# EV75E52A_R3_2-PHYs.net
KiCad netlist of a schematic drawn in Altium Designer
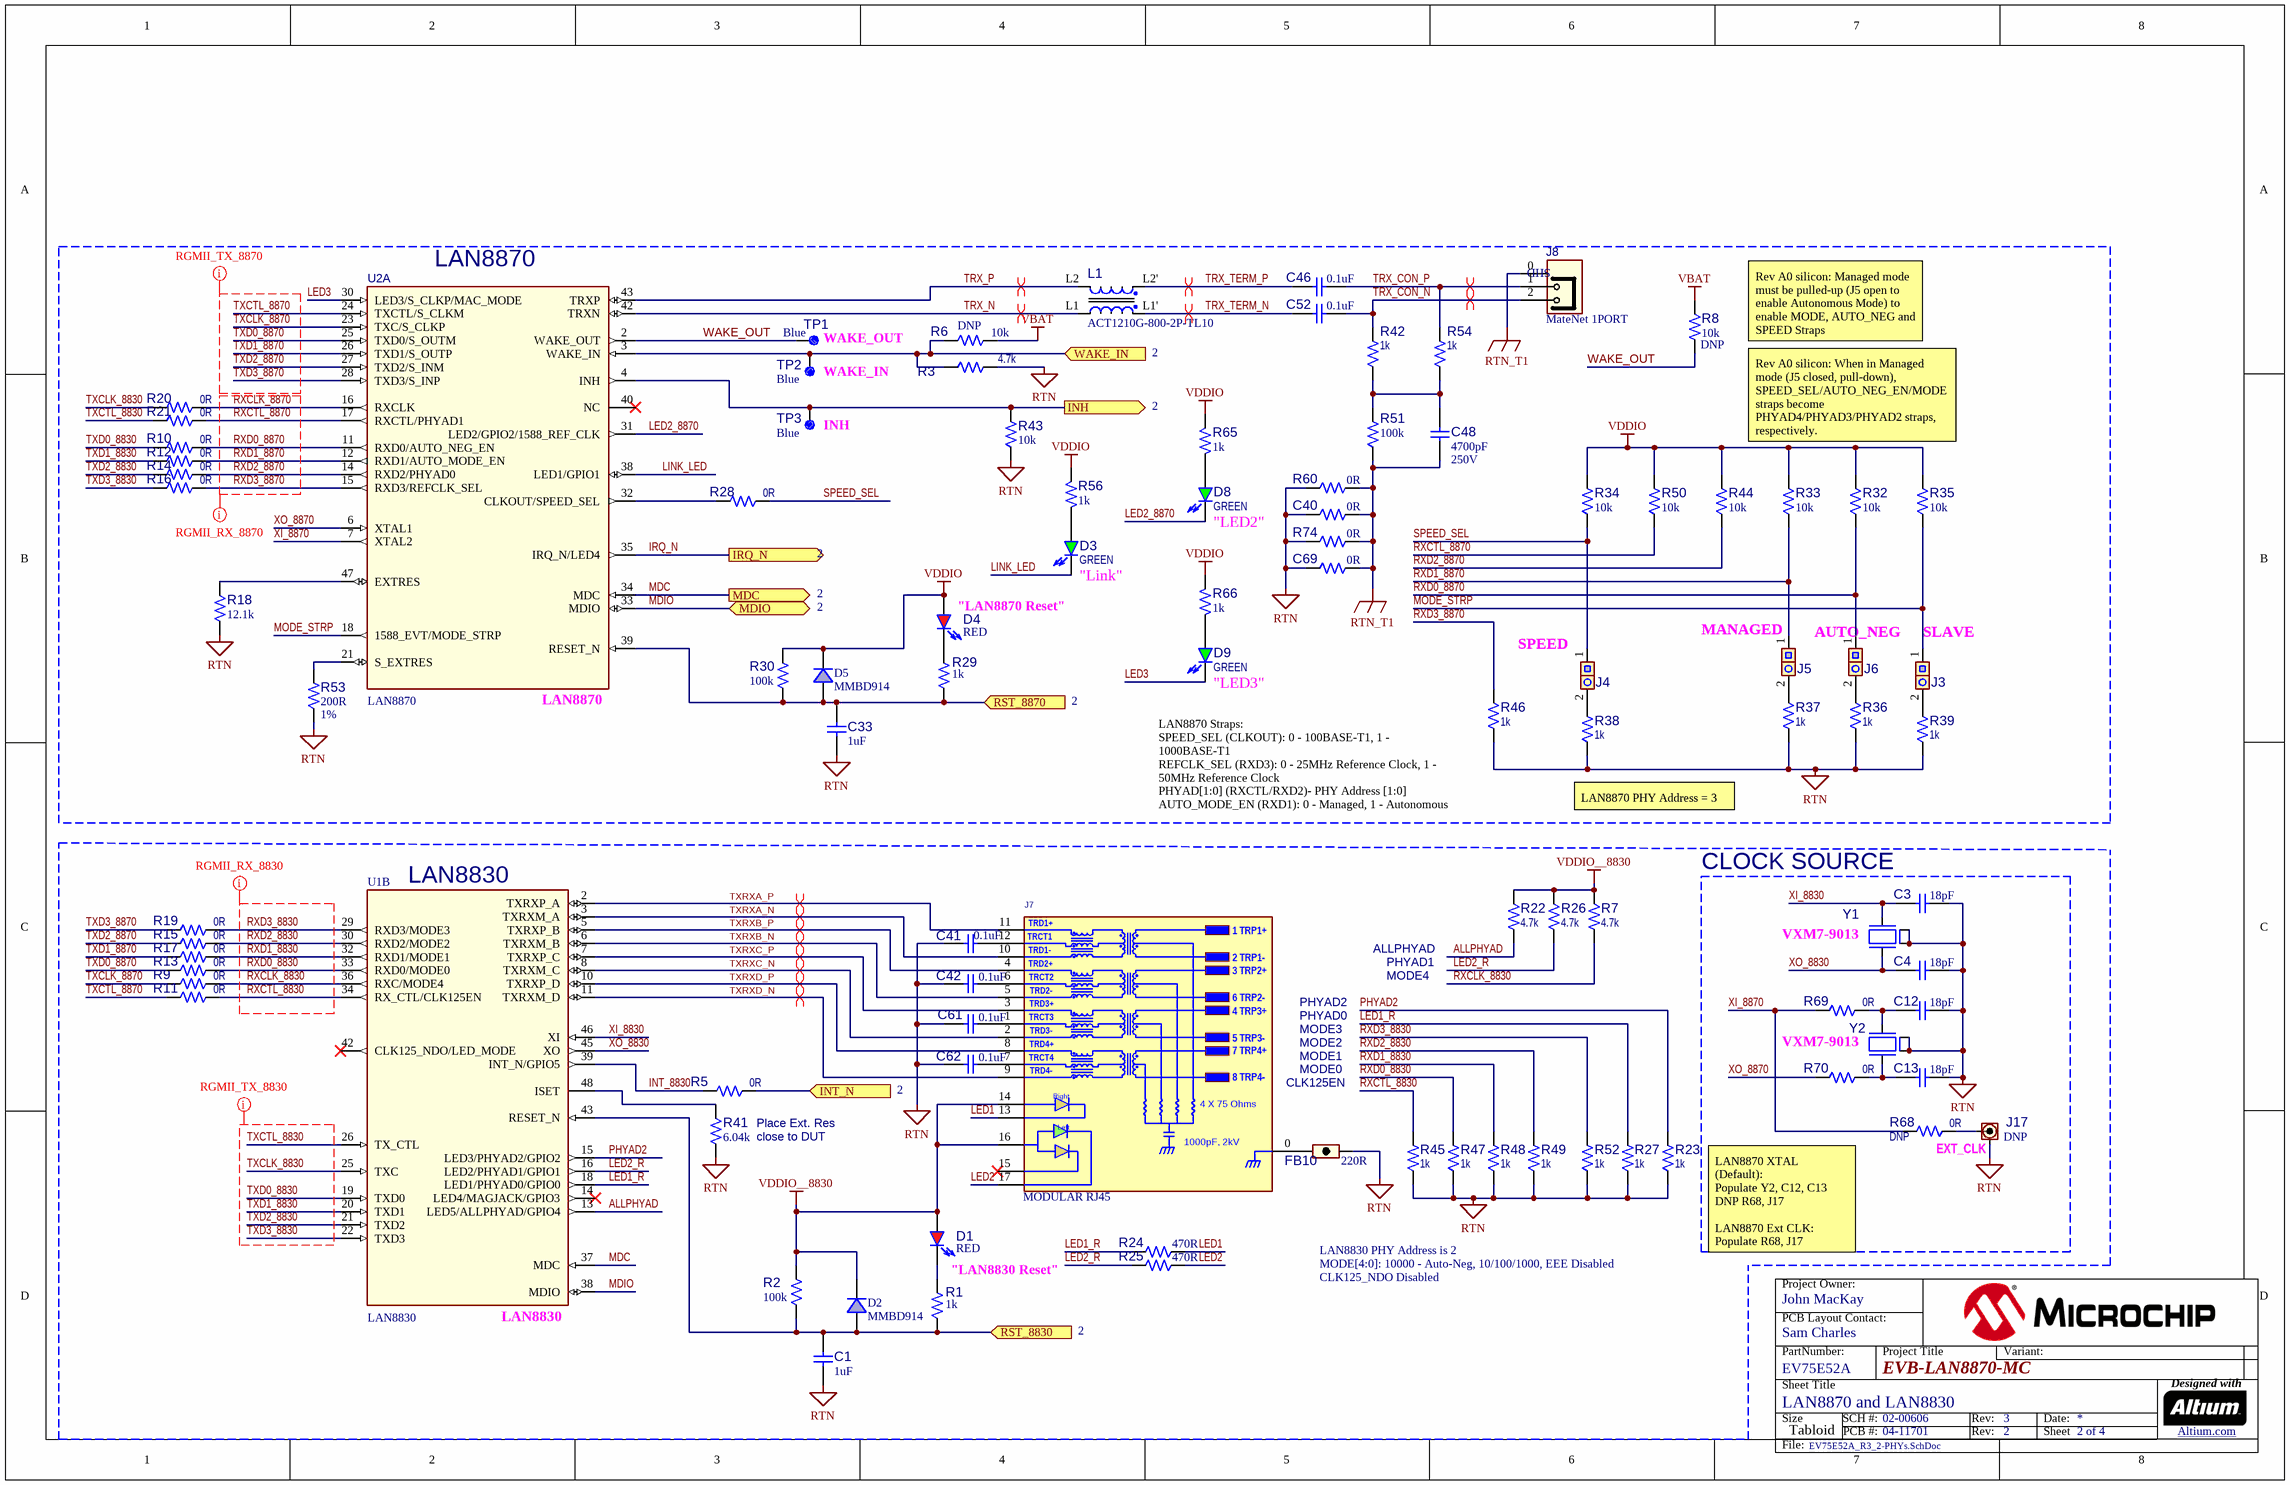
[diagram p0: EV75E52A_R3_2-PHYs.SchDoc]

(export (version "E")
  (design (tool "Eeschema 10.0.6"))
  (components
    (comp (ref "C1")
      (value "1uF")
      (footprint "CAP_C_0603")
      (description "Capacitor")
      (fields (field (name "VOLTAGE") "16V") (field (name "TOLERANCE") "10%"))
      (libsource (lib "MCHP-CDB") (part "Capacitor NP"))
    )
    (comp (ref "C3")
      (value "18pF")
      (footprint "CAP_C_0402")
      (description "Capacitor")
      (fields
        (field (name "VOLTAGE") "50V")
        (field (name "TOLERANCE") "5%")
        (field (name "OWNER") "Tad Ahlvers")
      )
      (libsource (lib "MCHP-CDB") (part "Capacitor NP"))
    )
    (comp (ref "C4")
      (value "18pF")
      (footprint "CAP_C_0402")
      (description "Capacitor")
      (fields
        (field (name "VOLTAGE") "50V")
        (field (name "TOLERANCE") "5%")
        (field (name "OWNER") "Tad Ahlvers")
      )
      (libsource (lib "MCHP-CDB") (part "Capacitor NP"))
    )
    (comp (ref "C12")
      (value "18pF")
      (footprint "CAP_C_0402")
      (description "Capacitor")
      (fields
        (field (name "VOLTAGE") "50V")
        (field (name "TOLERANCE") "5%")
        (field (name "OWNER") "Tad Ahlvers")
      )
      (libsource (lib "MCHP-CDB") (part "Capacitor NP"))
    )
    (comp (ref "C13")
      (value "18pF")
      (footprint "CAP_C_0402")
      (description "Capacitor")
      (fields
        (field (name "VOLTAGE") "50V")
        (field (name "TOLERANCE") "5%")
        (field (name "OWNER") "Tad Ahlvers")
      )
      (libsource (lib "MCHP-CDB") (part "Capacitor NP"))
    )
    (comp (ref "C33")
      (value "1uF")
      (footprint "CAP_C_0603")
      (description "Capacitor")
      (fields (field (name "VOLTAGE") "16V") (field (name "TOLERANCE") "10%"))
      (libsource (lib "MCHP-CDB") (part "Capacitor NP"))
    )
    (comp (ref "C40")
      (value "0R")
      (footprint "RES_C_0603")
      (description "Resistor")
      (fields (field (name "POWER") "1/10W") (field (name "OWNER") "Steve Dziaba"))
      (libsource (lib "MCHP-CDB") (part "Resistor"))
    )
    (comp (ref "C41")
      (value "0.1uF")
      (footprint "CAP_C_0402")
      (description "Capacitor")
      (fields
        (field (name "TOLERANCE") "10%")
        (field (name "VOLTAGE") "50V")
        (field (name "OWNER") "Jamus Griego")
      )
      (libsource (lib "MCHP-CDB-Offline") (part "Capacitor NP"))
    )
    (comp (ref "C42")
      (value "0.1uF")
      (footprint "CAP_C_0402")
      (description "Capacitor")
      (fields
        (field (name "TOLERANCE") "10%")
        (field (name "VOLTAGE") "50V")
        (field (name "OWNER") "Jamus Griego")
      )
      (libsource (lib "MCHP-CDB-Offline") (part "Capacitor NP"))
    )
    (comp (ref "C46")
      (value "0.1uF")
      (footprint "CAP_C_0805")
      (description "Capacitor")
      (fields
        (field (name "VOLTAGE") "250V")
        (field (name "TOLERANCE") "10%")
        (field (name "OWNER") "Cristian Papuc")
      )
      (libsource (lib "MCHP-CDB") (part "Capacitor NP"))
    )
    (comp (ref "C48")
      (value "4700pF")
      (footprint "CAP_C_0805")
      (fields
        (field (name "VOLTAGE") "250V")
        (field (name "TOLERANCE") "10%")
        (field (name "Comment") "Capacitor NP")
        (field (name "OWNER") "Darius Rydahl")
      )
      (libsource (lib "") (part "Capacitor NP_1"))
    )
    (comp (ref "C52")
      (value "0.1uF")
      (footprint "CAP_C_0805")
      (description "Capacitor")
      (fields
        (field (name "VOLTAGE") "250V")
        (field (name "TOLERANCE") "10%")
        (field (name "OWNER") "Cristian Papuc")
      )
      (libsource (lib "MCHP-CDB") (part "Capacitor NP"))
    )
    (comp (ref "C61")
      (value "0.1uF")
      (footprint "CAP_C_0402")
      (description "Capacitor")
      (fields
        (field (name "TOLERANCE") "10%")
        (field (name "VOLTAGE") "50V")
        (field (name "OWNER") "Jamus Griego")
      )
      (libsource (lib "MCHP-CDB-Offline") (part "Capacitor NP"))
    )
    (comp (ref "C62")
      (value "0.1uF")
      (footprint "CAP_C_0402")
      (description "Capacitor")
      (fields
        (field (name "TOLERANCE") "10%")
        (field (name "VOLTAGE") "50V")
        (field (name "OWNER") "Jamus Griego")
      )
      (libsource (lib "MCHP-CDB-Offline") (part "Capacitor NP"))
    )
    (comp (ref "C69")
      (value "0R")
      (footprint "RES_C_0603")
      (description "Resistor")
      (fields (field (name "POWER") "1/10W") (field (name "OWNER") "Steve Dziaba"))
      (libsource (lib "MCHP-CDB") (part "Resistor"))
    )
    (comp (ref "D1")
      (value "RED")
      (footprint "LED_0603_RED")
      (description "LED")
      (fields
        (field (name "LEGEND NOTE") "\"LAN8830 Reset\"")
        (field (name "Comment") "LED_red")
        (field (name "OWNER") "Sompoch Loboonlert")
      )
      (libsource (lib "MCHP-CDB") (part "LED_red"))
    )
    (comp (ref "D2")
      (value "MMBD914")
      (footprint "SOT-23-3")
      (fields (field (name "POWER") "10mW") (field (name "OWNER") "Sam Charles"))
      (libsource (lib "MCHP-CDB") (part "Diode Single SOT-23-3"))
    )
    (comp (ref "D3")
      (value "GREEN")
      (footprint "LED_0603_GREEN")
      (description "LED")
      (fields
        (field (name "POWER") "75mW")
        (field (name "LEGEND NOTES") "\"Link\"")
        (field (name "Comment") "LED_green")
        (field (name "OWNER") "Tad Ahlvers")
      )
      (libsource (lib "MCHP-CDB") (part "LED_green"))
    )
    (comp (ref "D4")
      (value "RED")
      (footprint "LED_0603_RED")
      (description "LED")
      (fields
        (field (name "LEGEND NOTE") "\"LAN8870 Reset\"")
        (field (name "Comment") "LED_red")
        (field (name "OWNER") "Sompoch Loboonlert")
      )
      (libsource (lib "MCHP-CDB") (part "LED_red"))
    )
    (comp (ref "D5")
      (value "MMBD914")
      (footprint "SOT-23-3")
      (fields (field (name "POWER") "10mW") (field (name "OWNER") "Sam Charles"))
      (libsource (lib "MCHP-CDB") (part "Diode Single SOT-23-3"))
    )
    (comp (ref "D8")
      (value "GREEN")
      (footprint "LED_0603_GREEN")
      (description "LED")
      (fields
        (field (name "POWER") "75mW")
        (field (name "LEGEND NOTES") "\"LED2\"")
        (field (name "Comment") "LED_green")
        (field (name "OWNER") "Tad Ahlvers")
      )
      (libsource (lib "MCHP-CDB") (part "LED_green"))
    )
    (comp (ref "D9")
      (value "GREEN")
      (footprint "LED_0603_GREEN")
      (description "LED")
      (fields
        (field (name "POWER") "75mW")
        (field (name "LEGEND NOTES") "\"LED3\"")
        (field (name "Comment") "LED_green")
        (field (name "OWNER") "Tad Ahlvers")
      )
      (libsource (lib "MCHP-CDB") (part "LED_green"))
    )
    (comp (ref "FB10")
      (value "220R")
      (footprint "IND_C_0603")
      (description "FERRITE 180R 1.5A SMD 0603")
      (fields (field (name "Comment") "Ferrite Bead") (field (name "OWNER") "Sam Charles"))
      (libsource (lib "MCHP-CDB") (part "Ferrite Bead"))
    )
    (comp (ref "J3")
      (value "Header 1x2")
      (footprint "HDR_M_2.54_1x2")
      (fields (field (name "LEGEND NOTES") "SLAVE") (field (name "OWNER") "Bogdan P (M91398)"))
      (libsource (lib "MCHP-CDB") (part "Header 1x2"))
    )
    (comp (ref "J4")
      (value "Header 1x2")
      (footprint "HDR_M_2.54_1x2")
      (fields (field (name "LEGEND NOTES") "SPEED") (field (name "OWNER") "Bogdan P (M91398)"))
      (libsource (lib "MCHP-CDB") (part "Header 1x2"))
    )
    (comp (ref "J5")
      (value "Header 1x2")
      (footprint "HDR_M_2.54_1x2")
      (fields (field (name "LEGEND NOTES") "MANAGED") (field (name "OWNER") "Bogdan P (M91398)"))
      (libsource (lib "MCHP-CDB") (part "Header 1x2"))
    )
    (comp (ref "J6")
      (value "Header 1x2")
      (footprint "HDR_M_2.54_1x2")
      (fields (field (name "LEGEND NOTES") "AUTO_NEG") (field (name "OWNER") "Bogdan P (M91398)"))
      (libsource (lib "MCHP-CDB") (part "Header 1x2"))
    )
    (comp (ref "J7")
      (value "MODULAR RJ45")
      (footprint "CON_JACK_RJ45_L829-1J1T-43")
      (fields (field (name "Comment") "CON_RJ-45_L829-1J1T-43") (field (name "OWNER") "Sam Charles"))
      (libsource (lib "MCHP-CDB") (part "CON_RJ-45_L829-1J1T-43"))
    )
    (comp (ref "J8")
      (value "MateNet 1PORT")
      (footprint "CON_2304372-9")
      (fields (field (name "Comment") "3PIN_WSHD") (field (name "OWNER") "Sam Charles"))
      (libsource (lib "MCHP-CDB") (part "3PIN_WSHD"))
    )
    (comp (ref "J17")
      (value "RF MMCX Female")
      (footprint "CON_MMCX_CINCH_135-3701-211")
      (description "CON Jack 2 Pins")
      (fields
        (field (name "POPULATED") "DNP")
        (field (name "LEGEND NOTE") "EXT_CLK")
        (field (name "OWNER") "Sam Charles")
      )
      (libsource (lib "MCHP-CDB") (part "CON Jack 2 Pins"))
    )
    (comp (ref "L1")
      (value "Inductor Choke")
      (footprint "IND_TDK_ACT1210L-201-2P_L3.9W2.5H2.5")
      (description "Inductor")
      (fields
        (field (name "MANUFACTURER PART NUMBER 1") "ACT1210G-800-2P-TL10")
        (field (name "OWNER") "Sam Charles")
      )
      (libsource (lib "MCHP-CDB") (part "Inductor Choke"))
    )
    (comp (ref "R1")
      (value "1k")
      (footprint "RES_C_0603")
      (description "Resistor")
      (fields
        (field (name "TOLERANCE") "5%")
        (field (name "VOLTAGE") "75V")
        (field (name "OWNER") "Bogdan P (M91398)")
      )
      (libsource (lib "") (part "Resistor_1"))
    )
    (comp (ref "R2")
      (value "100k")
      (footprint "RES_C_0603")
      (description "Resistor")
      (fields (field (name "TOLERANCE") "1%") (field (name "VOLTAGE") "75V"))
      (libsource (lib "") (part "Resistor_1"))
    )
    (comp (ref "R3")
      (value "4.7k")
      (footprint "RES_C_0402")
      (description "Resistor")
      (fields
        (field (name "TOLERANCE") "1%")
        (field (name "POWER") "1/16W")
        (field (name "OWNER") "Mike Ragsdale")
      )
      (libsource (lib "") (part "Resistor_1"))
    )
    (comp (ref "R5")
      (value "0R")
      (footprint "RES_C_0402")
      (description "Resistor")
      (fields (field (name "POWER") "1/16W") (field (name "OWNER") "Sompoch Loboonlert"))
      (libsource (lib "") (part "Resistor_1"))
    )
    (comp (ref "R6")
      (value "10k")
      (footprint "RES_C_0402")
      (description "Resistor")
      (fields
        (field (name "TOLERANCE") "1%")
        (field (name "VOLTAGE") "50V")
        (field (name "POPULATED") "DNP")
        (field (name "OWNER") "Jose Garcia")
      )
      (libsource (lib "") (part "Resistor_1"))
    )
    (comp (ref "R7")
      (value "4.7k")
      (footprint "RES_C_0402")
      (description "Resistor")
      (fields
        (field (name "TOLERANCE") "1%")
        (field (name "POWER") "1/16W")
        (field (name "OWNER") "Mike Ragsdale")
      )
      (libsource (lib "") (part "Resistor_1"))
    )
    (comp (ref "R8")
      (value "10k")
      (footprint "RES_C_0402")
      (description "Resistor")
      (fields
        (field (name "TOLERANCE") "1%")
        (field (name "VOLTAGE") "50V")
        (field (name "POPULATED") "DNP")
        (field (name "OWNER") "Jose Garcia")
      )
      (libsource (lib "") (part "Resistor_1"))
    )
    (comp (ref "R9")
      (value "0R")
      (footprint "RES_C_0402")
      (description "Resistor")
      (fields (field (name "POWER") "1/16W") (field (name "OWNER") "Sompoch Loboonlert"))
      (libsource (lib "") (part "Resistor_1"))
    )
    (comp (ref "R10")
      (value "0R")
      (footprint "RES_C_0402")
      (description "Resistor")
      (fields (field (name "POWER") "1/16W") (field (name "OWNER") "Sompoch Loboonlert"))
      (libsource (lib "") (part "Resistor_1"))
    )
    (comp (ref "R11")
      (value "0R")
      (footprint "RES_C_0402")
      (description "Resistor")
      (fields (field (name "POWER") "1/16W") (field (name "OWNER") "Sompoch Loboonlert"))
      (libsource (lib "") (part "Resistor_1"))
    )
    (comp (ref "R12")
      (value "0R")
      (footprint "RES_C_0402")
      (description "Resistor")
      (fields (field (name "POWER") "1/16W") (field (name "OWNER") "Sompoch Loboonlert"))
      (libsource (lib "") (part "Resistor_1"))
    )
    (comp (ref "R13")
      (value "0R")
      (footprint "RES_C_0402")
      (description "Resistor")
      (fields (field (name "POWER") "1/16W") (field (name "OWNER") "Sompoch Loboonlert"))
      (libsource (lib "") (part "Resistor_1"))
    )
    (comp (ref "R14")
      (value "0R")
      (footprint "RES_C_0402")
      (description "Resistor")
      (fields (field (name "POWER") "1/16W") (field (name "OWNER") "Sompoch Loboonlert"))
      (libsource (lib "") (part "Resistor_1"))
    )
    (comp (ref "R15")
      (value "0R")
      (footprint "RES_C_0402")
      (description "Resistor")
      (fields (field (name "POWER") "1/16W") (field (name "OWNER") "Sompoch Loboonlert"))
      (libsource (lib "") (part "Resistor_1"))
    )
    (comp (ref "R16")
      (value "0R")
      (footprint "RES_C_0402")
      (description "Resistor")
      (fields (field (name "POWER") "1/16W") (field (name "OWNER") "Sompoch Loboonlert"))
      (libsource (lib "") (part "Resistor_1"))
    )
    (comp (ref "R17")
      (value "0R")
      (footprint "RES_C_0402")
      (description "Resistor")
      (fields (field (name "POWER") "1/16W") (field (name "OWNER") "Sompoch Loboonlert"))
      (libsource (lib "") (part "Resistor_1"))
    )
    (comp (ref "R18")
      (value "12.1k")
      (footprint "RES_C_0402")
      (description "Resistor")
      (fields
        (field (name "TOLERANCE") "1%")
        (field (name "VOLTAGE") "50V")
        (field (name "OWNER") "Mike Ragsdale")
      )
      (libsource (lib "MCHP-CDB") (part "Resistor"))
    )
    (comp (ref "R19")
      (value "0R")
      (footprint "RES_C_0402")
      (description "Resistor")
      (fields (field (name "POWER") "1/16W") (field (name "OWNER") "Sompoch Loboonlert"))
      (libsource (lib "") (part "Resistor_1"))
    )
    (comp (ref "R20")
      (value "0R")
      (footprint "RES_C_0402")
      (description "Resistor")
      (fields (field (name "POWER") "1/16W") (field (name "OWNER") "Sompoch Loboonlert"))
      (libsource (lib "") (part "Resistor_1"))
    )
    (comp (ref "R21")
      (value "0R")
      (footprint "RES_C_0402")
      (description "Resistor")
      (fields (field (name "POWER") "1/16W") (field (name "OWNER") "Sompoch Loboonlert"))
      (libsource (lib "") (part "Resistor_1"))
    )
    (comp (ref "R22")
      (value "4.7k")
      (footprint "RES_C_0402")
      (description "Resistor")
      (fields
        (field (name "TOLERANCE") "1%")
        (field (name "POWER") "1/16W")
        (field (name "OWNER") "Mike Ragsdale")
      )
      (libsource (lib "") (part "Resistor_1"))
    )
    (comp (ref "R23")
      (value "1k")
      (footprint "RES_C_0402")
      (description "Resistor")
      (fields
        (field (name "TOLERANCE") "0.1%")
        (field (name "VOLTAGE") "50V")
        (field (name "OWNER") "Jose Garcia")
      )
      (libsource (lib "") (part "Resistor_1"))
    )
    (comp (ref "R24")
      (value "470R")
      (footprint "RES_C_0402")
      (description "Resistor")
      (fields (field (name "TOLERANCE") "5%") (field (name "VOLTAGE") "50V"))
      (libsource (lib "MCHP-CDB") (part "Resistor"))
    )
    (comp (ref "R25")
      (value "470R")
      (footprint "RES_C_0402")
      (description "Resistor")
      (fields (field (name "TOLERANCE") "5%") (field (name "VOLTAGE") "50V"))
      (libsource (lib "MCHP-CDB") (part "Resistor"))
    )
    (comp (ref "R26")
      (value "4.7k")
      (footprint "RES_C_0402")
      (description "Resistor")
      (fields
        (field (name "TOLERANCE") "1%")
        (field (name "POWER") "1/16W")
        (field (name "OWNER") "Mike Ragsdale")
      )
      (libsource (lib "") (part "Resistor_1"))
    )
    (comp (ref "R27")
      (value "1k")
      (footprint "RES_C_0402")
      (description "Resistor")
      (fields
        (field (name "TOLERANCE") "0.1%")
        (field (name "VOLTAGE") "50V")
        (field (name "OWNER") "Jose Garcia")
      )
      (libsource (lib "") (part "Resistor_1"))
    )
    (comp (ref "R28")
      (value "0R")
      (footprint "RES_C_0402")
      (description "Resistor")
      (fields (field (name "POWER") "1/16W") (field (name "OWNER") "Sompoch Loboonlert"))
      (libsource (lib "") (part "Resistor_1"))
    )
    (comp (ref "R29")
      (value "1k")
      (footprint "RES_C_0603")
      (description "Resistor")
      (fields
        (field (name "TOLERANCE") "5%")
        (field (name "VOLTAGE") "75V")
        (field (name "OWNER") "Bogdan P (M91398)")
      )
      (libsource (lib "") (part "Resistor_1"))
    )
    (comp (ref "R30")
      (value "100k")
      (footprint "RES_C_0603")
      (description "Resistor")
      (fields (field (name "TOLERANCE") "1%") (field (name "VOLTAGE") "75V"))
      (libsource (lib "") (part "Resistor_1"))
    )
    (comp (ref "R32")
      (value "10k")
      (footprint "RES_C_0402")
      (description "Resistor")
      (fields
        (field (name "TOLERANCE") "1%")
        (field (name "VOLTAGE") "50V")
        (field (name "OWNER") "Jose Garcia")
      )
      (libsource (lib "") (part "Resistor_1"))
    )
    (comp (ref "R33")
      (value "10k")
      (footprint "RES_C_0402")
      (description "Resistor")
      (fields
        (field (name "TOLERANCE") "1%")
        (field (name "VOLTAGE") "50V")
        (field (name "OWNER") "Jose Garcia")
      )
      (libsource (lib "") (part "Resistor_1"))
    )
    (comp (ref "R34")
      (value "10k")
      (footprint "RES_C_0402")
      (description "Resistor")
      (fields
        (field (name "TOLERANCE") "1%")
        (field (name "VOLTAGE") "50V")
        (field (name "OWNER") "Jose Garcia")
      )
      (libsource (lib "") (part "Resistor_1"))
    )
    (comp (ref "R35")
      (value "10k")
      (footprint "RES_C_0402")
      (description "Resistor")
      (fields
        (field (name "TOLERANCE") "1%")
        (field (name "VOLTAGE") "50V")
        (field (name "OWNER") "Jose Garcia")
      )
      (libsource (lib "") (part "Resistor_1"))
    )
    (comp (ref "R36")
      (value "1k")
      (footprint "RES_C_0402")
      (description "Resistor")
      (fields
        (field (name "TOLERANCE") "0.1%")
        (field (name "VOLTAGE") "50V")
        (field (name "OWNER") "Jose Garcia")
      )
      (libsource (lib "") (part "Resistor_1"))
    )
    (comp (ref "R37")
      (value "1k")
      (footprint "RES_C_0402")
      (description "Resistor")
      (fields
        (field (name "TOLERANCE") "0.1%")
        (field (name "VOLTAGE") "50V")
        (field (name "OWNER") "Jose Garcia")
      )
      (libsource (lib "") (part "Resistor_1"))
    )
    (comp (ref "R38")
      (value "1k")
      (footprint "RES_C_0402")
      (description "Resistor")
      (fields
        (field (name "TOLERANCE") "0.1%")
        (field (name "VOLTAGE") "50V")
        (field (name "OWNER") "Jose Garcia")
      )
      (libsource (lib "") (part "Resistor_1"))
    )
    (comp (ref "R39")
      (value "1k")
      (footprint "RES_C_0402")
      (description "Resistor")
      (fields
        (field (name "TOLERANCE") "0.1%")
        (field (name "VOLTAGE") "50V")
        (field (name "OWNER") "Jose Garcia")
      )
      (libsource (lib "") (part "Resistor_1"))
    )
    (comp (ref "R41")
      (value "6.04k")
      (footprint "RES_C_0402")
      (description "Resistor")
      (fields
        (field (name "TOLERANCE") "1%")
        (field (name "VOLTAGE") "50V")
        (field (name "OWNER") "Severino Balong Jr.")
      )
      (libsource (lib "MCHP-CDB") (part "Resistor"))
    )
    (comp (ref "R42")
      (value "1k")
      (footprint "RES_C_1206")
      (description "Resistor")
      (fields
        (field (name "TOLERANCE") "1%")
        (field (name "VOLTAGE") "200V")
        (field (name "OWNER") "Mark Loper")
      )
      (libsource (lib "") (part "Resistor_1"))
    )
    (comp (ref "R43")
      (value "10k")
      (footprint "RES_C_0402")
      (description "Resistor")
      (fields
        (field (name "TOLERANCE") "1%")
        (field (name "VOLTAGE") "50V")
        (field (name "OWNER") "Jose Garcia")
      )
      (libsource (lib "") (part "Resistor_1"))
    )
    (comp (ref "R44")
      (value "10k")
      (footprint "RES_C_0402")
      (description "Resistor")
      (fields
        (field (name "TOLERANCE") "1%")
        (field (name "VOLTAGE") "50V")
        (field (name "OWNER") "Jose Garcia")
      )
      (libsource (lib "") (part "Resistor_1"))
    )
    (comp (ref "R45")
      (value "1k")
      (footprint "RES_C_0402")
      (description "Resistor")
      (fields
        (field (name "TOLERANCE") "0.1%")
        (field (name "VOLTAGE") "50V")
        (field (name "OWNER") "Jose Garcia")
      )
      (libsource (lib "") (part "Resistor_1"))
    )
    (comp (ref "R46")
      (value "1k")
      (footprint "RES_C_0402")
      (description "Resistor")
      (fields
        (field (name "TOLERANCE") "0.1%")
        (field (name "VOLTAGE") "50V")
        (field (name "OWNER") "Jose Garcia")
      )
      (libsource (lib "") (part "Resistor_1"))
    )
    (comp (ref "R47")
      (value "1k")
      (footprint "RES_C_0402")
      (description "Resistor")
      (fields
        (field (name "TOLERANCE") "0.1%")
        (field (name "VOLTAGE") "50V")
        (field (name "OWNER") "Jose Garcia")
      )
      (libsource (lib "") (part "Resistor_1"))
    )
    (comp (ref "R48")
      (value "1k")
      (footprint "RES_C_0402")
      (description "Resistor")
      (fields
        (field (name "TOLERANCE") "0.1%")
        (field (name "VOLTAGE") "50V")
        (field (name "OWNER") "Jose Garcia")
      )
      (libsource (lib "") (part "Resistor_1"))
    )
    (comp (ref "R49")
      (value "1k")
      (footprint "RES_C_0402")
      (description "Resistor")
      (fields
        (field (name "TOLERANCE") "0.1%")
        (field (name "VOLTAGE") "50V")
        (field (name "OWNER") "Jose Garcia")
      )
      (libsource (lib "") (part "Resistor_1"))
    )
    (comp (ref "R50")
      (value "10k")
      (footprint "RES_C_0402")
      (description "Resistor")
      (fields
        (field (name "TOLERANCE") "1%")
        (field (name "VOLTAGE") "50V")
        (field (name "OWNER") "Jose Garcia")
      )
      (libsource (lib "") (part "Resistor_1"))
    )
    (comp (ref "R51")
      (value "100k")
      (footprint "RES_C_0603")
      (description "Resistor")
      (fields (field (name "TOLERANCE") "1%") (field (name "VOLTAGE") "75V"))
      (libsource (lib "") (part "Resistor_1"))
    )
    (comp (ref "R52")
      (value "1k")
      (footprint "RES_C_0402")
      (description "Resistor")
      (fields
        (field (name "TOLERANCE") "0.1%")
        (field (name "VOLTAGE") "50V")
        (field (name "OWNER") "Jose Garcia")
      )
      (libsource (lib "") (part "Resistor_1"))
    )
    (comp (ref "R53")
      (value "200R")
      (footprint "RES_C_0402")
      (description "Resistor")
      (fields (field (name "TOLERANCE") "1%") (field (name "VOLTAGE") "50V") (field (name "POWER") "1/10W"))
      (libsource (lib "MCHP-CDB") (part "Resistor"))
    )
    (comp (ref "R54")
      (value "1k")
      (footprint "RES_C_1206")
      (description "Resistor")
      (fields
        (field (name "TOLERANCE") "1%")
        (field (name "VOLTAGE") "200V")
        (field (name "OWNER") "Mark Loper")
      )
      (libsource (lib "") (part "Resistor_1"))
    )
    (comp (ref "R56")
      (value "1k")
      (footprint "RES_C_0603")
      (description "Resistor")
      (fields (field (name "TOLERANCE") "1%") (field (name "VOLTAGE") "75V"))
      (libsource (lib "") (part "Resistor_1"))
    )
    (comp (ref "R60")
      (value "0R")
      (footprint "RES_C_0603")
      (description "Resistor")
      (fields (field (name "POWER") "1/10W") (field (name "OWNER") "Steve Dziaba"))
      (libsource (lib "MCHP-CDB") (part "Resistor"))
    )
    (comp (ref "R65")
      (value "1k")
      (footprint "RES_C_0603")
      (description "Resistor")
      (fields (field (name "TOLERANCE") "1%") (field (name "VOLTAGE") "75V"))
      (libsource (lib "") (part "Resistor_1"))
    )
    (comp (ref "R66")
      (value "1k")
      (footprint "RES_C_0603")
      (description "Resistor")
      (fields (field (name "TOLERANCE") "1%") (field (name "VOLTAGE") "75V"))
      (libsource (lib "") (part "Resistor_1"))
    )
    (comp (ref "R68")
      (value "0R")
      (footprint "RES_C_0402")
      (description "Resistor")
      (fields
        (field (name "POWER") "1/16W")
        (field (name "POPULATED") "DNP")
        (field (name "OWNER") "Sompoch Loboonlert")
      )
      (libsource (lib "") (part "Resistor_1"))
    )
    (comp (ref "R69")
      (value "0R")
      (footprint "RES_C_0402")
      (description "Resistor")
      (fields (field (name "POWER") "1/16W") (field (name "OWNER") "Sompoch Loboonlert"))
      (libsource (lib "") (part "Resistor_1"))
    )
    (comp (ref "R70")
      (value "0R")
      (footprint "RES_C_0402")
      (description "Resistor")
      (fields (field (name "POWER") "1/16W") (field (name "OWNER") "Sompoch Loboonlert"))
      (libsource (lib "") (part "Resistor_1"))
    )
    (comp (ref "R74")
      (value "0R")
      (footprint "RES_C_0603")
      (description "Resistor")
      (fields (field (name "POWER") "1/10W") (field (name "OWNER") "Steve Dziaba"))
      (libsource (lib "MCHP-CDB") (part "Resistor"))
    )
    (comp (ref "TP1")
      (value "Blue")
      (footprint "CON_TP_TH_V_BLUE_KEC_5117")
      (description "Test Point")
      (fields (field (name "LEGEND NOTE") "WAKE_OUT") (field (name "OWNER") "Sam Charles"))
      (libsource (lib "MCHP-CDB") (part "Test Point"))
    )
    (comp (ref "TP2")
      (value "Blue")
      (footprint "CON_TP_TH_V_BLUE_KEC_5117")
      (description "Test Point")
      (fields (field (name "LEGEND NOTE") "WAKE_IN") (field (name "OWNER") "Sam Charles"))
      (libsource (lib "MCHP-CDB") (part "Test Point"))
    )
    (comp (ref "TP3")
      (value "Blue")
      (footprint "CON_TP_TH_V_BLUE_KEC_5117")
      (description "Test Point")
      (fields (field (name "LEGEND NOTE") "INH") (field (name "OWNER") "Sam Charles"))
      (libsource (lib "MCHP-CDB") (part "Test Point"))
    )
    (comp (ref "U1")
      (value "LAN8830")
      (footprint "QFN-48_7x7_EP5.15x5.15")
      (fields
        (field (name "LEGEND NOTE") "LAN8830")
        (field (name "Comment") "LAN8830 QFN-48")
        (field (name "OWNER") "Sam Charles")
      )
      (libsource (lib "MCHP-CDB") (part "LAN8830 QFN-48"))
    )
    (comp (ref "U2")
      (value "LAN8870")
      (footprint "QFN-48_7x7_EP5.1x5.1")
      (fields
        (field (name "LEGEND NOTE") "LAN8870")
        (field (name "Comment") "LAN8870 QFN-48")
        (field (name "OWNER") "Sam Charles")
      )
      (libsource (lib "LAN8870 QFN-48") (part "LAN8870 QFN-48"))
    )
    (comp (ref "Y1")
      (value "Crystal 4 Pins")
      (footprint "CRYSTAL_L3.2W2.5H0.8")
      (fields (field (name "LEGEND NOTE") "VXM7-9013") (field (name "OWNER") "Sam Charles"))
      (libsource (lib "MCHP-CDB") (part "Crystal 4 Pins"))
    )
    (comp (ref "Y2")
      (value "Crystal 4 Pins")
      (footprint "CRYSTAL_L3.2W2.5H0.8")
      (fields (field (name "OWNER") "Sam Charles"))
      (libsource (lib "MCHP-CDB") (part "Crystal 4 Pins"))
    )
  )
  (nets
    (net (code "1") (name "/ALLPHYAD") (class "Default")
      (node (ref "R22") (pin "1") (pinfunction "1_1") (pintype "passive"))
      (node (ref "U1") (pin "13") (pinfunction "LED5/ALLPHYAD/GPIO4_13") (pintype "output"))
    )
    (net (code "2") (name "/INH") (class "Default")
      (node (ref "R43") (pin "2") (pinfunction "2_2") (pintype "passive"))
      (node (ref "TP3") (pin "1") (pinfunction "1_1") (pintype "passive"))
      (node (ref "U2") (pin "4") (pinfunction "INH_4") (pintype "output"))
    )
    (net (code "3") (name "/INT_8830") (class "Default")
      (node (ref "R5") (pin "1") (pinfunction "1_1") (pintype "passive"))
      (node (ref "U1") (pin "39") (pinfunction "INT_N/GPIO5_39") (pintype "output"))
    )
    (net (code "4") (name "/INT_N") (class "Default")
      (node (ref "R5") (pin "2") (pinfunction "2_2") (pintype "passive"))
    )
    (net (code "5") (name "/IRQ_N") (class "Default")
      (node (ref "U2") (pin "35") (pinfunction "IRQ_N/LED4_35") (pintype "output"))
    )
    (net (code "6") (name "/LED1") (class "Default")
      (node (ref "J7") (pin "13") (pinfunction "13_13") (pintype "passive"))
      (node (ref "R24") (pin "2") (pinfunction "2_2") (pintype "passive"))
    )
    (net (code "7") (name "/LED1_R") (class "Default")
      (node (ref "R24") (pin "1") (pinfunction "1_1") (pintype "passive"))
      (node (ref "R27") (pin "2") (pinfunction "2_2") (pintype "passive"))
      (node (ref "U1") (pin "18") (pinfunction "LED1/PHYAD0/GPIO0_18") (pintype "output"))
    )
    (net (code "8") (name "/LED2") (class "Default")
      (node (ref "J7") (pin "17") (pinfunction "17_17") (pintype "passive"))
      (node (ref "R25") (pin "2") (pinfunction "2_2") (pintype "passive"))
    )
    (net (code "9") (name "/LED2_8870") (class "Default")
      (node (ref "D8") (pin "2") (pinfunction "K_2") (pintype "passive"))
      (node (ref "U2") (pin "31") (pinfunction "LED2/GPIO2/1588_REF_CLK_31") (pintype "output"))
    )
    (net (code "10") (name "/LED2_R") (class "Default")
      (node (ref "R25") (pin "1") (pinfunction "1_1") (pintype "passive"))
      (node (ref "R26") (pin "1") (pinfunction "1_1") (pintype "passive"))
      (node (ref "U1") (pin "16") (pinfunction "LED2/PHYAD1/GPIO1_16") (pintype "output"))
    )
    (net (code "11") (name "/LED3") (class "Default")
      (node (ref "D9") (pin "2") (pinfunction "K_2") (pintype "passive"))
      (node (ref "U2") (pin "30") (pinfunction "LED3/S_CLKP/MAC_MODE_30") (pintype "input"))
    )
    (net (code "12") (name "/LINK_LED") (class "Default")
      (node (ref "D3") (pin "2") (pinfunction "K_2") (pintype "passive"))
      (node (ref "U2") (pin "38") (pinfunction "LED1/GPIO1_38") (pintype "bidirectional"))
    )
    (net (code "13") (name "/MDC") (class "Default")
      (node (ref "U1") (pin "37") (pinfunction "MDC_37") (pintype "input"))
      (node (ref "U2") (pin "34") (pinfunction "MDC_34") (pintype "input"))
    )
    (net (code "14") (name "/MDIO") (class "Default")
      (node (ref "U1") (pin "38") (pinfunction "MDIO_38") (pintype "bidirectional"))
      (node (ref "U2") (pin "33") (pinfunction "MDIO_33") (pintype "bidirectional"))
    )
    (net (code "15") (name "/MODE_STRP") (class "Default")
      (node (ref "J3") (pin "1") (pinfunction "1_1") (pintype "passive"))
      (node (ref "R35") (pin "1") (pinfunction "1_1") (pintype "passive"))
      (node (ref "U2") (pin "18") (pinfunction "1588_EVT/MODE_STRP_18") (pintype "output"))
    )
    (net (code "16") (name "/PHYAD2") (class "Default")
      (node (ref "R23") (pin "2") (pinfunction "2_2") (pintype "passive"))
      (node (ref "U1") (pin "15") (pinfunction "LED3/PHYAD2/GPIO2_15") (pintype "output"))
    )
    (net (code "17") (name "/RST_8830") (class "Default")
      (node (ref "C1") (pin "2") (pinfunction "2_2") (pintype "passive"))
      (node (ref "D2") (pin "1") (pinfunction "A_1") (pintype "passive"))
      (node (ref "R1") (pin "2") (pinfunction "2_2") (pintype "passive"))
      (node (ref "R2") (pin "1") (pinfunction "1_1") (pintype "passive"))
      (node (ref "U1") (pin "43") (pinfunction "RESET_N_43") (pintype "input"))
    )
    (net (code "18") (name "/RST_8870") (class "Default")
      (node (ref "C33") (pin "2") (pinfunction "2_2") (pintype "passive"))
      (node (ref "D5") (pin "1") (pinfunction "A_1") (pintype "passive"))
      (node (ref "R29") (pin "2") (pinfunction "2_2") (pintype "passive"))
      (node (ref "R30") (pin "1") (pinfunction "1_1") (pintype "passive"))
      (node (ref "U2") (pin "39") (pinfunction "RESET_N_39") (pintype "input"))
    )
    (net (code "19") (name "/RXCLK_8830") (class "Default")
      (node (ref "R7") (pin "1") (pinfunction "1_1") (pintype "passive"))
      (node (ref "R9") (pin "2") (pinfunction "2_2") (pintype "passive"))
      (node (ref "U1") (pin "36") (pinfunction "RXC/MODE4_36") (pintype "output"))
    )
    (net (code "20") (name "/RXCLK_8870") (class "Default")
      (node (ref "R20") (pin "2") (pinfunction "2_2") (pintype "passive"))
      (node (ref "U2") (pin "16") (pinfunction "RXCLK_16") (pintype "output"))
    )
    (net (code "21") (name "/RXCTL_8830") (class "Default")
      (node (ref "R11") (pin "2") (pinfunction "2_2") (pintype "passive"))
      (node (ref "R45") (pin "2") (pinfunction "2_2") (pintype "passive"))
      (node (ref "U1") (pin "34") (pinfunction "RX_CTL/CLK125EN_34") (pintype "output"))
    )
    (net (code "22") (name "/RXCTL_8870") (class "Default")
      (node (ref "R21") (pin "2") (pinfunction "2_2") (pintype "passive"))
      (node (ref "R50") (pin "1") (pinfunction "1_1") (pintype "passive"))
      (node (ref "U2") (pin "17") (pinfunction "RXCTL/PHYAD1_17") (pintype "output"))
    )
    (net (code "23") (name "/RXD0_8830") (class "Default")
      (node (ref "R13") (pin "2") (pinfunction "2_2") (pintype "passive"))
      (node (ref "R47") (pin "2") (pinfunction "2_2") (pintype "passive"))
      (node (ref "U1") (pin "33") (pinfunction "RXD0/MODE0_33") (pintype "output"))
    )
    (net (code "24") (name "/RXD0_8870") (class "Default")
      (node (ref "J6") (pin "1") (pinfunction "1_1") (pintype "passive"))
      (node (ref "R10") (pin "2") (pinfunction "2_2") (pintype "passive"))
      (node (ref "R32") (pin "1") (pinfunction "1_1") (pintype "passive"))
      (node (ref "U2") (pin "11") (pinfunction "RXD0/AUTO_NEG_EN_11") (pintype "output"))
    )
    (net (code "25") (name "/RXD1_8830") (class "Default")
      (node (ref "R17") (pin "2") (pinfunction "2_2") (pintype "passive"))
      (node (ref "R48") (pin "2") (pinfunction "2_2") (pintype "passive"))
      (node (ref "U1") (pin "32") (pinfunction "RXD1/MODE1_32") (pintype "output"))
    )
    (net (code "26") (name "/RXD1_8870") (class "Default")
      (node (ref "J5") (pin "1") (pinfunction "1_1") (pintype "passive"))
      (node (ref "R12") (pin "2") (pinfunction "2_2") (pintype "passive"))
      (node (ref "R33") (pin "1") (pinfunction "1_1") (pintype "passive"))
      (node (ref "U2") (pin "12") (pinfunction "RXD1/AUTO_MODE_EN_12") (pintype "output"))
    )
    (net (code "27") (name "/RXD2_8830") (class "Default")
      (node (ref "R15") (pin "2") (pinfunction "2_2") (pintype "passive"))
      (node (ref "R49") (pin "2") (pinfunction "2_2") (pintype "passive"))
      (node (ref "U1") (pin "30") (pinfunction "RXD2/MODE2_30") (pintype "output"))
    )
    (net (code "28") (name "/RXD2_8870") (class "Default")
      (node (ref "R14") (pin "2") (pinfunction "2_2") (pintype "passive"))
      (node (ref "R44") (pin "1") (pinfunction "1_1") (pintype "passive"))
      (node (ref "U2") (pin "14") (pinfunction "RXD2/PHYAD0_14") (pintype "output"))
    )
    (net (code "29") (name "/RXD3_8830") (class "Default")
      (node (ref "R19") (pin "2") (pinfunction "2_2") (pintype "passive"))
      (node (ref "R52") (pin "2") (pinfunction "2_2") (pintype "passive"))
      (node (ref "U1") (pin "29") (pinfunction "RXD3/MODE3_29") (pintype "output"))
    )
    (net (code "30") (name "/RXD3_8870") (class "Default")
      (node (ref "R16") (pin "2") (pinfunction "2_2") (pintype "passive"))
      (node (ref "R46") (pin "2") (pinfunction "2_2") (pintype "passive"))
      (node (ref "U2") (pin "15") (pinfunction "RXD3/REFCLK_SEL_15") (pintype "output"))
    )
    (net (code "31") (name "/SPEED_SEL") (class "Default")
      (node (ref "J4") (pin "1") (pinfunction "1_1") (pintype "passive"))
      (node (ref "R28") (pin "2") (pinfunction "2_2") (pintype "passive"))
      (node (ref "R34") (pin "1") (pinfunction "1_1") (pintype "passive"))
    )
    (net (code "32") (name "/TRX_CON_N") (class "Default")
      (node (ref "C52") (pin "1") (pinfunction "1_1") (pintype "passive"))
      (node (ref "J8") (pin "2") (pinfunction "2_2") (pintype "passive"))
      (node (ref "R42") (pin "2") (pinfunction "2_2") (pintype "passive"))
    )
    (net (code "33") (name "/TRX_CON_P") (class "Default")
      (node (ref "C46") (pin "1") (pinfunction "1_1") (pintype "passive"))
      (node (ref "J8") (pin "1") (pinfunction "1_1") (pintype "passive"))
      (node (ref "R54") (pin "2") (pinfunction "2_2") (pintype "passive"))
    )
    (net (code "34") (name "/TRX_N") (class "Default")
      (node (ref "L1") (pin "L1") (pinfunction "L1_L1") (pintype "passive"))
      (node (ref "U2") (pin "42") (pinfunction "TRXN_42") (pintype "bidirectional"))
    )
    (net (code "35") (name "/TRX_P") (class "Default")
      (node (ref "L1") (pin "L2") (pinfunction "L2_L2") (pintype "passive"))
      (node (ref "U2") (pin "43") (pinfunction "TRXP_43") (pintype "bidirectional"))
    )
    (net (code "36") (name "/TRX_TERM_N") (class "Default")
      (node (ref "C52") (pin "2") (pinfunction "2_2") (pintype "passive"))
      (node (ref "L1") (pin "L1'") (pinfunction "L1'_L1'") (pintype "passive"))
    )
    (net (code "37") (name "/TRX_TERM_P") (class "Default")
      (node (ref "C46") (pin "2") (pinfunction "2_2") (pintype "passive"))
      (node (ref "L1") (pin "L2'") (pinfunction "L2'_L2'") (pintype "passive"))
    )
    (net (code "38") (name "/TXCLK_8830") (class "Default")
      (node (ref "R20") (pin "1") (pinfunction "1_1") (pintype "passive"))
      (node (ref "U1") (pin "25") (pinfunction "TXC_25") (pintype "input"))
    )
    (net (code "39") (name "/TXCLK_8870") (class "Default")
      (node (ref "R9") (pin "1") (pinfunction "1_1") (pintype "passive"))
      (node (ref "U2") (pin "23") (pinfunction "TXC/S_CLKP_23") (pintype "input"))
    )
    (net (code "40") (name "/TXCTL_8830") (class "Default")
      (node (ref "R21") (pin "1") (pinfunction "1_1") (pintype "passive"))
      (node (ref "U1") (pin "26") (pinfunction "TX_CTL_26") (pintype "input"))
    )
    (net (code "41") (name "/TXCTL_8870") (class "Default")
      (node (ref "R11") (pin "1") (pinfunction "1_1") (pintype "passive"))
      (node (ref "U2") (pin "24") (pinfunction "TXCTL/S_CLKM_24") (pintype "input"))
    )
    (net (code "42") (name "/TXD0_8830") (class "Default")
      (node (ref "R10") (pin "1") (pinfunction "1_1") (pintype "passive"))
      (node (ref "U1") (pin "19") (pinfunction "TXD0_19") (pintype "input"))
    )
    (net (code "43") (name "/TXD0_8870") (class "Default")
      (node (ref "R13") (pin "1") (pinfunction "1_1") (pintype "passive"))
      (node (ref "U2") (pin "25") (pinfunction "TXD0/S_OUTM_25") (pintype "input"))
    )
    (net (code "44") (name "/TXD1_8830") (class "Default")
      (node (ref "R12") (pin "1") (pinfunction "1_1") (pintype "passive"))
      (node (ref "U1") (pin "20") (pinfunction "TXD1_20") (pintype "input"))
    )
    (net (code "45") (name "/TXD1_8870") (class "Default")
      (node (ref "R17") (pin "1") (pinfunction "1_1") (pintype "passive"))
      (node (ref "U2") (pin "26") (pinfunction "TXD1/S_OUTP_26") (pintype "input"))
    )
    (net (code "46") (name "/TXD2_8830") (class "Default")
      (node (ref "R14") (pin "1") (pinfunction "1_1") (pintype "passive"))
      (node (ref "U1") (pin "21") (pinfunction "TXD2_21") (pintype "input"))
    )
    (net (code "47") (name "/TXD2_8870") (class "Default")
      (node (ref "R15") (pin "1") (pinfunction "1_1") (pintype "passive"))
      (node (ref "U2") (pin "27") (pinfunction "TXD2/S_INM_27") (pintype "input"))
    )
    (net (code "48") (name "/TXD3_8830") (class "Default")
      (node (ref "R16") (pin "1") (pinfunction "1_1") (pintype "passive"))
      (node (ref "U1") (pin "22") (pinfunction "TXD3_22") (pintype "input"))
    )
    (net (code "49") (name "/TXD3_8870") (class "Default")
      (node (ref "R19") (pin "1") (pinfunction "1_1") (pintype "passive"))
      (node (ref "U2") (pin "28") (pinfunction "TXD3/S_INP_28") (pintype "input"))
    )
    (net (code "50") (name "/TXRXA_N") (class "Default")
      (node (ref "J7") (pin "10") (pinfunction "10_10") (pintype "passive"))
      (node (ref "U1") (pin "3") (pinfunction "TXRXM_A_3") (pintype "bidirectional"))
    )
    (net (code "51") (name "/TXRXA_P") (class "Default")
      (node (ref "J7") (pin "11") (pinfunction "11_11") (pintype "passive"))
      (node (ref "U1") (pin "2") (pinfunction "TXRXP_A_2") (pintype "bidirectional"))
    )
    (net (code "52") (name "/TXRXB_N") (class "Default")
      (node (ref "J7") (pin "5") (pinfunction "5_5") (pintype "passive"))
      (node (ref "U1") (pin "6") (pinfunction "TXRXM_B_6") (pintype "bidirectional"))
    )
    (net (code "53") (name "/TXRXB_P") (class "Default")
      (node (ref "J7") (pin "4") (pinfunction "4_4") (pintype "passive"))
      (node (ref "U1") (pin "5") (pinfunction "TXRXP_B_5") (pintype "bidirectional"))
    )
    (net (code "54") (name "/TXRXC_N") (class "Default")
      (node (ref "J7") (pin "2") (pinfunction "2_2") (pintype "passive"))
      (node (ref "U1") (pin "8") (pinfunction "TXRXM_C_8") (pintype "bidirectional"))
    )
    (net (code "55") (name "/TXRXC_P") (class "Default")
      (node (ref "J7") (pin "3") (pinfunction "3_3") (pintype "passive"))
      (node (ref "U1") (pin "7") (pinfunction "TXRXP_C_7") (pintype "bidirectional"))
    )
    (net (code "56") (name "/TXRXD_N") (class "Default")
      (node (ref "J7") (pin "9") (pinfunction "9_9") (pintype "passive"))
      (node (ref "U1") (pin "11") (pinfunction "TXRXM_D_11") (pintype "bidirectional"))
    )
    (net (code "57") (name "/TXRXD_P") (class "Default")
      (node (ref "J7") (pin "8") (pinfunction "8_8") (pintype "passive"))
      (node (ref "U1") (pin "10") (pinfunction "TXRXP_D_10") (pintype "bidirectional"))
    )
    (net (code "58") (name "/WAKE_IN") (class "Default")
      (node (ref "R3") (pin "2") (pinfunction "2_2") (pintype "passive"))
      (node (ref "R6") (pin "2") (pinfunction "2_2") (pintype "passive"))
      (node (ref "TP2") (pin "1") (pinfunction "1_1") (pintype "passive"))
      (node (ref "U2") (pin "3") (pinfunction "WAKE_IN_3") (pintype "input"))
    )
    (net (code "59") (name "/WAKE_OUT") (class "Default")
      (node (ref "R8") (pin "1") (pinfunction "1_1") (pintype "passive"))
      (node (ref "TP1") (pin "1") (pinfunction "1_1") (pintype "passive"))
      (node (ref "U2") (pin "2") (pinfunction "WAKE_OUT_2") (pintype "output"))
    )
    (net (code "60") (name "/XI_8830") (class "Default")
      (node (ref "C3") (pin "1") (pinfunction "1_1") (pintype "passive"))
      (node (ref "U1") (pin "46") (pinfunction "XI_46") (pintype "input"))
      (node (ref "Y1") (pin "3") (pinfunction "Osc2_3") (pintype "passive"))
    )
    (net (code "61") (name "/XI_8870") (class "Default")
      (node (ref "R68") (pin "1") (pinfunction "1_1") (pintype "passive"))
      (node (ref "R69") (pin "1") (pinfunction "1_1") (pintype "passive"))
      (node (ref "U2") (pin "7") (pinfunction "XTAL2_7") (pintype "output"))
    )
    (net (code "62") (name "/XO_8830") (class "Default")
      (node (ref "C4") (pin "1") (pinfunction "1_1") (pintype "passive"))
      (node (ref "U1") (pin "45") (pinfunction "XO_45") (pintype "output"))
      (node (ref "Y1") (pin "1") (pinfunction "Osc1_1") (pintype "passive"))
    )
    (net (code "63") (name "/XO_8870") (class "Default")
      (node (ref "R70") (pin "1") (pinfunction "1_1") (pintype "passive"))
      (node (ref "U2") (pin "6") (pinfunction "XTAL1_6") (pintype "input"))
    )
    (net (code "64") (name "Net-(C41-Pad2)") (class "Default")
      (node (ref "C41") (pin "2") (pinfunction "2_2") (pintype "passive"))
      (node (ref "J7") (pin "12") (pinfunction "12_12") (pintype "passive"))
    )
    (net (code "65") (name "Net-(C42-Pad2)") (class "Default")
      (node (ref "C42") (pin "2") (pinfunction "2_2") (pintype "passive"))
      (node (ref "J7") (pin "6") (pinfunction "6_6") (pintype "passive"))
    )
    (net (code "66") (name "Net-(C48-Pad2)") (class "Default")
      (node (ref "C48") (pin "2") (pinfunction "2_2") (pintype "passive"))
      (node (ref "R42") (pin "1") (pinfunction "1_1") (pintype "passive"))
      (node (ref "R51") (pin "2") (pinfunction "2_2") (pintype "passive"))
      (node (ref "R54") (pin "1") (pinfunction "1_1") (pintype "passive"))
    )
    (net (code "67") (name "Net-(C61-Pad2)") (class "Default")
      (node (ref "C61") (pin "2") (pinfunction "2_2") (pintype "passive"))
      (node (ref "J7") (pin "1") (pinfunction "1_1") (pintype "passive"))
    )
    (net (code "68") (name "Net-(C62-Pad2)") (class "Default")
      (node (ref "C62") (pin "2") (pinfunction "2_2") (pintype "passive"))
      (node (ref "J7") (pin "7") (pinfunction "7_7") (pintype "passive"))
    )
    (net (code "69") (name "Net-(D1-K)") (class "Default")
      (node (ref "D1") (pin "2") (pinfunction "K_2") (pintype "passive"))
      (node (ref "R1") (pin "1") (pinfunction "1_1") (pintype "passive"))
    )
    (net (code "70") (name "Net-(D3-A)") (class "Default")
      (node (ref "D3") (pin "1") (pinfunction "A_1") (pintype "passive"))
      (node (ref "R56") (pin "2") (pinfunction "2_2") (pintype "passive"))
    )
    (net (code "71") (name "Net-(D4-K)") (class "Default")
      (node (ref "D4") (pin "2") (pinfunction "K_2") (pintype "passive"))
      (node (ref "R29") (pin "1") (pinfunction "1_1") (pintype "passive"))
    )
    (net (code "72") (name "Net-(D8-A)") (class "Default")
      (node (ref "D8") (pin "1") (pinfunction "A_1") (pintype "passive"))
      (node (ref "R65") (pin "2") (pinfunction "2_2") (pintype "passive"))
    )
    (net (code "73") (name "Net-(D9-A)") (class "Default")
      (node (ref "D9") (pin "1") (pinfunction "A_1") (pintype "passive"))
      (node (ref "R66") (pin "2") (pinfunction "2_2") (pintype "passive"))
    )
    (net (code "74") (name "Net-(J3-Pad2)") (class "Default")
      (node (ref "J3") (pin "2") (pinfunction "2_2") (pintype "passive"))
      (node (ref "R39") (pin "2") (pinfunction "2_2") (pintype "passive"))
    )
    (net (code "75") (name "Net-(J4-Pad2)") (class "Default")
      (node (ref "J4") (pin "2") (pinfunction "2_2") (pintype "passive"))
      (node (ref "R38") (pin "2") (pinfunction "2_2") (pintype "passive"))
    )
    (net (code "76") (name "Net-(J5-Pad2)") (class "Default")
      (node (ref "J5") (pin "2") (pinfunction "2_2") (pintype "passive"))
      (node (ref "R37") (pin "2") (pinfunction "2_2") (pintype "passive"))
    )
    (net (code "77") (name "Net-(J6-Pad2)") (class "Default")
      (node (ref "J6") (pin "2") (pinfunction "2_2") (pintype "passive"))
      (node (ref "R36") (pin "2") (pinfunction "2_2") (pintype "passive"))
    )
    (net (code "78") (name "Net-(J7-SHLD)") (class "Default")
      (node (ref "FB10") (pin "1") (pinfunction "1_1") (pintype "passive"))
      (node (ref "J7") (pin "0") (pinfunction "SHLD_0") (pintype "power_in"))
    )
    (net (code "79") (name "Net-(J17-Pad1)") (class "Default")
      (node (ref "J17") (pin "1") (pinfunction "1_1") (pintype "passive"))
      (node (ref "R68") (pin "2") (pinfunction "2_2") (pintype "passive"))
    )
    (net (code "80") (name "Net-(U1B-ISET)") (class "Default")
      (node (ref "R41") (pin "2") (pinfunction "2_2") (pintype "passive"))
      (node (ref "U1") (pin "48") (pinfunction "ISET_48") (pintype "passive"))
    )
    (net (code "81") (name "Net-(U2A-CLKOUT{slash}SPEED_SEL)") (class "Default")
      (node (ref "R28") (pin "1") (pinfunction "1_1") (pintype "passive"))
      (node (ref "U2") (pin "32") (pinfunction "CLKOUT/SPEED_SEL_32") (pintype "output"))
    )
    (net (code "82") (name "Net-(U2A-EXTRES)") (class "Default")
      (node (ref "R18") (pin "2") (pinfunction "2_2") (pintype "passive"))
      (node (ref "U2") (pin "47") (pinfunction "EXTRES_47") (pintype "bidirectional"))
    )
    (net (code "83") (name "Net-(U2A-S_EXTRES)") (class "Default")
      (node (ref "R53") (pin "2") (pinfunction "2_2") (pintype "passive"))
      (node (ref "U2") (pin "21") (pinfunction "S_EXTRES_21") (pintype "bidirectional"))
    )
    (net (code "84") (name "Net-(Y2-Osc1)") (class "Default")
      (node (ref "C13") (pin "1") (pinfunction "1_1") (pintype "passive"))
      (node (ref "R70") (pin "2") (pinfunction "2_2") (pintype "passive"))
      (node (ref "Y2") (pin "1") (pinfunction "Osc1_1") (pintype "passive"))
    )
    (net (code "85") (name "Net-(Y2-Osc2)") (class "Default")
      (node (ref "C12") (pin "1") (pinfunction "1_1") (pintype "passive"))
      (node (ref "R69") (pin "2") (pinfunction "2_2") (pintype "passive"))
      (node (ref "Y2") (pin "3") (pinfunction "Osc2_3") (pintype "passive"))
    )
    (net (code "86") (name "RTN") (class "Default")
      (node (ref "C1") (pin "1") (pinfunction "1_1") (pintype "passive"))
      (node (ref "C12") (pin "2") (pinfunction "2_2") (pintype "passive"))
      (node (ref "C13") (pin "2") (pinfunction "2_2") (pintype "passive"))
      (node (ref "C3") (pin "2") (pinfunction "2_2") (pintype "passive"))
      (node (ref "C33") (pin "1") (pinfunction "1_1") (pintype "passive"))
      (node (ref "C4") (pin "2") (pinfunction "2_2") (pintype "passive"))
      (node (ref "C40") (pin "1") (pinfunction "1_1") (pintype "passive"))
      (node (ref "C41") (pin "1") (pinfunction "1_1") (pintype "passive"))
      (node (ref "C42") (pin "1") (pinfunction "1_1") (pintype "passive"))
      (node (ref "C61") (pin "1") (pinfunction "1_1") (pintype "passive"))
      (node (ref "C62") (pin "1") (pinfunction "1_1") (pintype "passive"))
      (node (ref "C69") (pin "1") (pinfunction "1_1") (pintype "passive"))
      (node (ref "FB10") (pin "2") (pinfunction "2_2") (pintype "passive"))
      (node (ref "J17") (pin "2") (pinfunction "2_2") (pintype "passive"))
      (node (ref "R18") (pin "1") (pinfunction "1_1") (pintype "passive"))
      (node (ref "R23") (pin "1") (pinfunction "1_1") (pintype "passive"))
      (node (ref "R27") (pin "1") (pinfunction "1_1") (pintype "passive"))
      (node (ref "R3") (pin "1") (pinfunction "1_1") (pintype "passive"))
      (node (ref "R36") (pin "1") (pinfunction "1_1") (pintype "passive"))
      (node (ref "R37") (pin "1") (pinfunction "1_1") (pintype "passive"))
      (node (ref "R38") (pin "1") (pinfunction "1_1") (pintype "passive"))
      (node (ref "R39") (pin "1") (pinfunction "1_1") (pintype "passive"))
      (node (ref "R41") (pin "1") (pinfunction "1_1") (pintype "passive"))
      (node (ref "R43") (pin "1") (pinfunction "1_1") (pintype "passive"))
      (node (ref "R45") (pin "1") (pinfunction "1_1") (pintype "passive"))
      (node (ref "R46") (pin "1") (pinfunction "1_1") (pintype "passive"))
      (node (ref "R47") (pin "1") (pinfunction "1_1") (pintype "passive"))
      (node (ref "R48") (pin "1") (pinfunction "1_1") (pintype "passive"))
      (node (ref "R49") (pin "1") (pinfunction "1_1") (pintype "passive"))
      (node (ref "R52") (pin "1") (pinfunction "1_1") (pintype "passive"))
      (node (ref "R53") (pin "1") (pinfunction "1_1") (pintype "passive"))
      (node (ref "R60") (pin "1") (pinfunction "1_1") (pintype "passive"))
      (node (ref "R74") (pin "1") (pinfunction "1_1") (pintype "passive"))
      (node (ref "Y1") (pin "2") (pinfunction "GND_2") (pintype "power_in"))
      (node (ref "Y1") (pin "4") (pinfunction "GND_4") (pintype "power_in"))
      (node (ref "Y2") (pin "2") (pinfunction "GND_2") (pintype "power_in"))
      (node (ref "Y2") (pin "4") (pinfunction "GND_4") (pintype "power_in"))
    )
    (net (code "87") (name "RTN_T1") (class "Default")
      (node (ref "C40") (pin "2") (pinfunction "2_2") (pintype "passive"))
      (node (ref "C48") (pin "1") (pinfunction "1_1") (pintype "passive"))
      (node (ref "C69") (pin "2") (pinfunction "2_2") (pintype "passive"))
      (node (ref "J8") (pin "0") (pinfunction "0_0") (pintype "passive"))
      (node (ref "R51") (pin "1") (pinfunction "1_1") (pintype "passive"))
      (node (ref "R60") (pin "2") (pinfunction "2_2") (pintype "passive"))
      (node (ref "R74") (pin "2") (pinfunction "2_2") (pintype "passive"))
    )
    (net (code "88") (name "VBAT") (class "Default")
      (node (ref "R6") (pin "1") (pinfunction "1_1") (pintype "passive"))
      (node (ref "R8") (pin "2") (pinfunction "2_2") (pintype "passive"))
    )
    (net (code "89") (name "VDDIO") (class "Default")
      (node (ref "D4") (pin "1") (pinfunction "A_1") (pintype "passive"))
      (node (ref "D5") (pin "3") (pinfunction "K_3") (pintype "passive"))
      (node (ref "R30") (pin "2") (pinfunction "2_2") (pintype "passive"))
      (node (ref "R32") (pin "2") (pinfunction "2_2") (pintype "passive"))
      (node (ref "R33") (pin "2") (pinfunction "2_2") (pintype "passive"))
      (node (ref "R34") (pin "2") (pinfunction "2_2") (pintype "passive"))
      (node (ref "R35") (pin "2") (pinfunction "2_2") (pintype "passive"))
      (node (ref "R44") (pin "2") (pinfunction "2_2") (pintype "passive"))
      (node (ref "R50") (pin "2") (pinfunction "2_2") (pintype "passive"))
      (node (ref "R56") (pin "1") (pinfunction "1_1") (pintype "passive"))
      (node (ref "R65") (pin "1") (pinfunction "1_1") (pintype "passive"))
      (node (ref "R66") (pin "1") (pinfunction "1_1") (pintype "passive"))
    )
    (net (code "90") (name "VDDIO__8830") (class "Default")
      (node (ref "D1") (pin "1") (pinfunction "A_1") (pintype "passive"))
      (node (ref "D2") (pin "3") (pinfunction "K_3") (pintype "passive"))
      (node (ref "J7") (pin "14") (pinfunction "14_14") (pintype "passive"))
      (node (ref "J7") (pin "16") (pinfunction "16_16") (pintype "passive"))
      (node (ref "R2") (pin "2") (pinfunction "2_2") (pintype "passive"))
      (node (ref "R22") (pin "2") (pinfunction "2_2") (pintype "passive"))
      (node (ref "R26") (pin "2") (pinfunction "2_2") (pintype "passive"))
      (node (ref "R7") (pin "2") (pinfunction "2_2") (pintype "passive"))
    )
    (net (code "91") (name "unconnected-(J7-Pad15)") (class "Default")
      (node (ref "J7") (pin "15") (pinfunction "15_15") (pintype "passive+no_connect"))
    )
    (net (code "92") (name "unconnected-(U1B-CLK125_NDO{slash}LED_MODE-Pad42)") (class "Default")
      (node (ref "U1") (pin "42") (pinfunction "CLK125_NDO/LED_MODE_42") (pintype "output+no_connect"))
    )
    (net (code "93") (name "unconnected-(U1B-LED4{slash}MAGJACK{slash}GPIO3-Pad14)") (class "Default")
      (node (ref "U1") (pin "14") (pinfunction "LED4/MAGJACK/GPIO3_14") (pintype "output+no_connect"))
    )
    (net (code "94") (name "unconnected-(U2A-NC-Pad40)") (class "Default")
      (node (ref "U2") (pin "40") (pinfunction "NC_40") (pintype "passive+no_connect"))
    )
  )
)
